# SUPPLY.net
KiCad netlist of a schematic drawn in Altium Designer
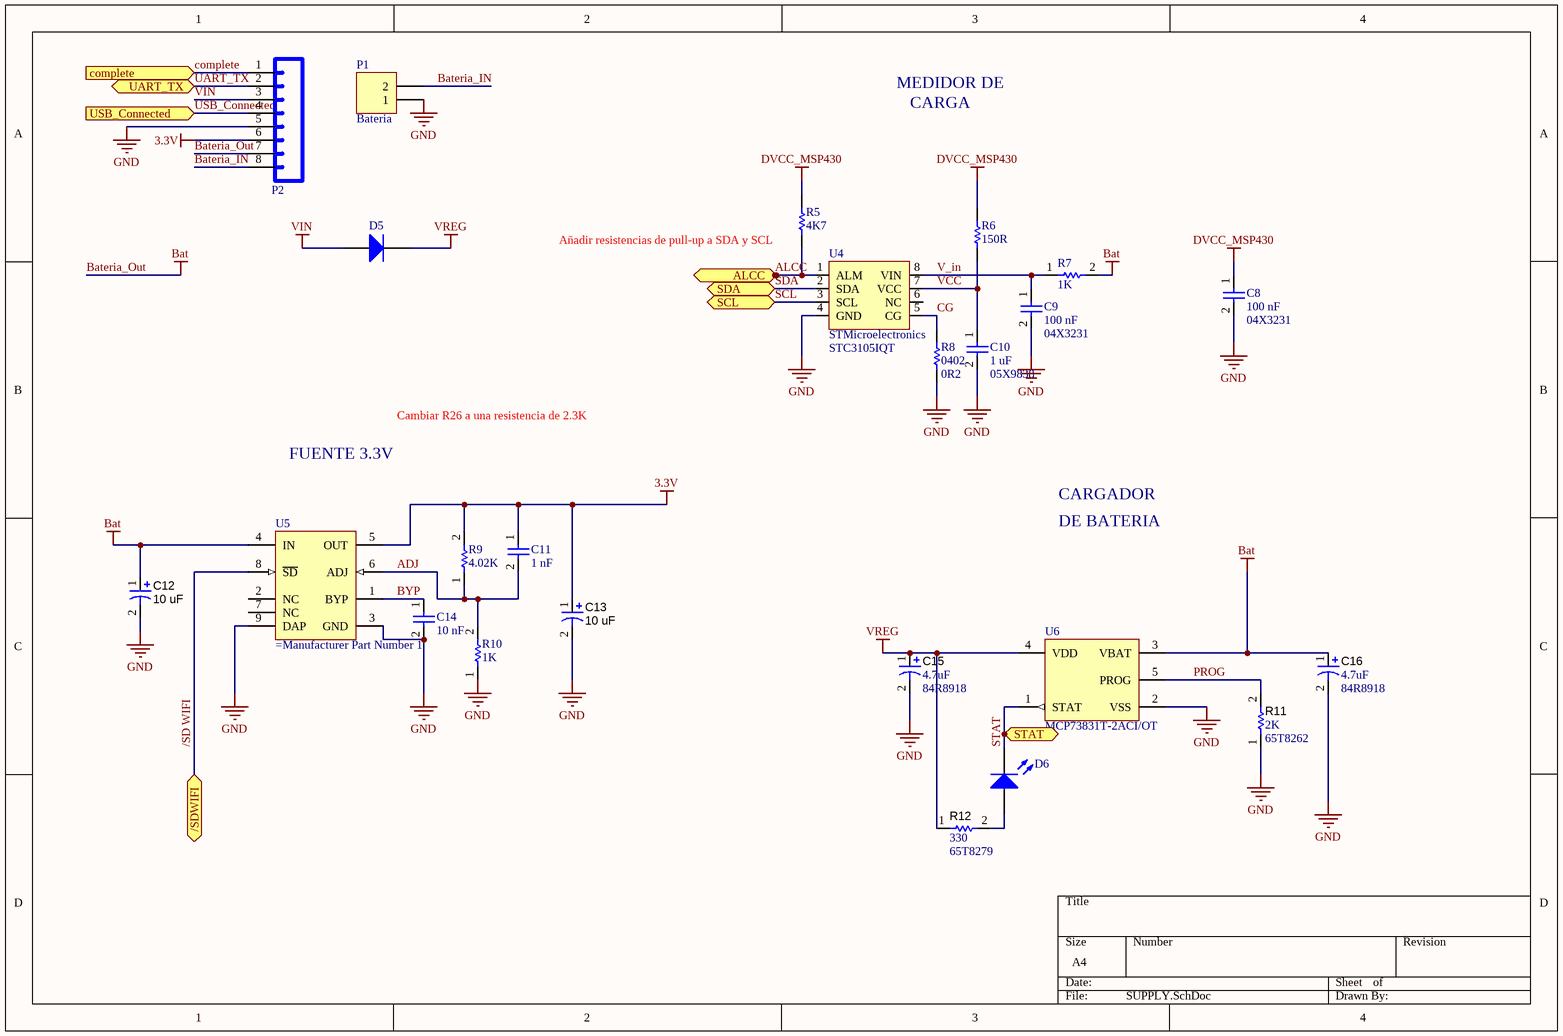
[diagram p0: SUPPLY.SchDoc]

(export (version "E")
  (design (tool "Eeschema 10.0.6"))
  (components
    (comp (ref "C8")
      (value "100 nF")
      (footprint "CR-0402")
      (description "TDK - C1005X7R1H104M050BB - CAP CERAMIC, 0.1UF, 50V, X7R, 0402")
      (fields (field (name "SUPPLIER PART NUMBER 1") "04X3231"))
      (libsource (lib "BASE OXIMETRO") (part "C1005X7R1H104M050BB"))
    )
    (comp (ref "C9")
      (value "100 nF")
      (footprint "CR-0402")
      (description "TDK - C1005X7R1H104M050BB - CAP CERAMIC, 0.1UF, 50V, X7R, 0402")
      (fields (field (name "SUPPLIER PART NUMBER 1") "04X3231"))
      (libsource (lib "BASE OXIMETRO") (part "C1005X7R1H104M050BB"))
    )
    (comp (ref "C10")
      (value "1 uF")
      (footprint "CR-0402")
      (description "TDK - C1005X5R1E105K050BC - CAP, MLCC, X5R, 1UF, 25V, 0402")
      (fields (field (name "SUPPLIER PART NUMBER 1") "05X9838"))
      (libsource (lib "BASE OXIMETRO") (part "C1005X5R1E105K050BC"))
    )
    (comp (ref "C11")
      (value "1 nF")
      (footprint "CR-0402")
      (description "TDK - C1005X7R1E102K050BA - CAPACITOR CERAMIC 1000PF, 25V, X7R, 10%, 0402")
      (libsource (lib "BASE OXIMETRO") (part "C1005X7R1E102K050BA"))
    )
    (comp (ref "C12")
      (value "10 uF")
      (footprint "C-0603")
      (description "NICHICON - F981A106MMA - CAPACITOR TANT, 10UF, 10V 20%")
      (libsource (lib "BASE OXIMETRO") (part "F981A106MMA"))
    )
    (comp (ref "C13")
      (value "10 uF")
      (footprint "C-0603")
      (description "NICHICON - F981A106MMA - CAPACITOR TANT, 10UF, 10V 20%")
      (libsource (lib "BASE OXIMETRO") (part "F981A106MMA"))
    )
    (comp (ref "C14")
      (value "10 nF")
      (footprint "CR-0402")
      (description "TDK - C1005X7R1H103K050BB - CAP CERAMIC, 0.01UF, 50V, X7R, 0402")
      (libsource (lib "BASE OXIMETRO") (part "C1005X7R1H103K050BB"))
    )
    (comp (ref "C15")
      (value "4.7uF")
      (footprint "C-0603")
      (description "CAP, TANTALUM, 4.7UF, 20%, 16V, 20 OHM, SMT0603")
      (fields
        (field (name "PART NUMBER") "F980J475MUA")
        (field (name "MANUFACTURER") "NICHICON")
        (field (name "SUPPLIER PART NUMBER 1") "84R8918")
      )
      (libsource (lib "BASE OXIMETRO") (part "F981C475MMA"))
    )
    (comp (ref "C16")
      (value "4.7uF")
      (footprint "C-0603")
      (description "CAP, TANTALUM, 4.7UF, 20%, 16V, 20 OHM, SMT0603")
      (fields
        (field (name "PART NUMBER") "F980J475MUA")
        (field (name "MANUFACTURER") "NICHICON")
        (field (name "SUPPLIER PART NUMBER 1") "84R8918")
      )
      (libsource (lib "BASE OXIMETRO") (part "F981C475MMA"))
    )
    (comp (ref "D5")
      (value "58K2394")
      (footprint "DO-214AA d")
      (description "Default Diode")
      (fields (field (name "PUBLISHER") "Altium Limited"))
      (libsource (lib "BASE OXIMETRO") (part "Diode"))
    )
    (comp (ref "D6")
      (value "LED0")
      (footprint "CR-0402")
      (description "LED Blue")
      (fields (field (name "PUBLISHER") "Altium Limited"))
      (libsource (lib "BASE OXIMETRO") (part "LED0"))
    )
    (comp (ref "P1")
      (value "Bateria")
      (footprint "HDR1X2")
      (description "Header, 2-Pin")
      (fields (field (name "PUBLISHER") "Altium Limited"))
      (libsource (lib "BASE OXIMETRO") (part "Header 2"))
    )
    (comp (ref "P2")
      (value "68000-236HLF")
      (footprint "HEAD8-NOSS")
      (description "HEADER 1X8")
      (fields (field (name "MANUFACTURER") "Amphenol FCI"))
      (libsource (lib "TarjetaPrincipalV1_4") (part "HEADER 1X8"))
    )
    (comp (ref "R5")
      (value "4K7")
      (footprint "CR-0402")
      (description "VISHAY DALE - CRCW02014K70FNED - THICK FILM RESISTOR, 4.7 KOHM, 50 mW, 1%, FULL REEL")
      (libsource (lib "BASE OXIMETRO") (part "CRCW02014K70FNED"))
    )
    (comp (ref "R6")
      (value "150R")
      (footprint "CR-0402")
      (description "VISHAY DALE - CRCW0201150RFNED - THICK FILM RESISTOR, 150 OHM, 50 mW, 1%, FULL REEL")
      (libsource (lib "BASE OXIMETRO") (part "CRCW0201150RFNED"))
    )
    (comp (ref "R7")
      (value "1K")
      (footprint "CR-0402")
      (description "VISHAY DALE - CRCW02011K00FNED - RESISTOR, THICK FILM CHIP, 1KOHM 50mW, 1%, FULL REEL")
      (libsource (lib "BASE OXIMETRO") (part "CRCW02011K00FNED"))
    )
    (comp (ref "R8")
      (value "0402")
      (footprint "R-0402")
      (description "PANASONIC ELECTRONIC COMPONENTS - ERJ-2BSFR20X - RESISTOR, 0.2OHM, 166mW, 1%, SMD")
      (fields (field (name "ALTIUM_VALUE") "0R2"))
      (libsource (lib "BASE OXIMETRO") (part "ERJ-2BSFR20X"))
    )
    (comp (ref "R9")
      (value "4.02K")
      (footprint "CR-0402")
      (description "VISHAY DALE - CRCW02014K02FNED - RESISTOR, THICK FILM, 4.02 KOHM, 50 mW, 1%, FULL REEL")
      (libsource (lib "BASE OXIMETRO") (part "CRCW02014K02FNED"))
    )
    (comp (ref "R10")
      (value "1K")
      (footprint "CR-0402")
      (description "VISHAY DALE - CRCW02011K00FNED - RESISTOR, THICK FILM CHIP, 1KOHM 50mW, 1%, FULL REEL")
      (libsource (lib "BASE OXIMETRO") (part "CRCW02011K00FNED"))
    )
    (comp (ref "R11")
      (value "2K")
      (footprint "CR-0402")
      (description "RESISTOR, THICK FILM, 2K, 5%, 0.1W, SMT0402")
      (fields
        (field (name "PART NUMBER") "ERJ-2GEJ202X")
        (field (name "PARTNUMBER") "PANASONIC")
        (field (name "SUPPLIER PART NUMBER 1") "65T8262")
      )
      (libsource (lib "BASE OXIMETRO") (part "ERJ-2GEJ202X"))
    )
    (comp (ref "R12")
      (value "330")
      (footprint "R-0402")
      (description "RESISTOR, THICK FILM, 330, 5%, 0.1W, SMT0402")
      (fields
        (field (name "PART NUMBER") "ERJ-2GEJ331X")
        (field (name "MANUFACTURER") "PANASONIC")
        (field (name "SUPPLIER PART NUMBER 1") "65T8279")
      )
      (libsource (lib "BASE OXIMETRO") (part "ERJ-2GEJ331X"))
    )
    (comp (ref "U4")
      (value "STMicroelectronics")
      (footprint "TDFN8")
      (description "IC BATTERY MON GAS GAUGE 8-TDFN")
      (fields (field (name "MANUFACTURER PART NUMBER 1") "STC3105IQT"))
      (libsource (lib "BASE OXIMETRO") (part "STC3105"))
    )
    (comp (ref "U5")
      (value "~")
      (footprint "SO8 DDA")
      (description "TEXAS INSTRUMENTS - LP3878MRX-ADJ/NOPB - IC, LDO REGULATOR, 800mA, 1-5.5V, FULL REEL")
      (libsource (lib "BASE OXIMETRO") (part "LP3878MRX-ADJ/NOPB"))
    )
    (comp (ref "U6")
      (value "MCP73831T-2ACI/OT")
      (footprint "SOT-23-5_3d")
      (fields (field (name "PUBLISHER") "Altium Limited"))
      (libsource (lib "BASE OXIMETRO") (part "MCP73831T-2ACI/OT"))
    )
  )
  (nets
    (net (code "1") (name "/ADJ") (class "Default")
      (node (ref "C11") (pin "2") (pinfunction "2_2") (pintype "passive"))
      (node (ref "R10") (pin "2") (pinfunction "2_2") (pintype "passive"))
      (node (ref "R9") (pin "1") (pinfunction "1_1") (pintype "passive"))
      (node (ref "U5") (pin "6") (pinfunction "ADJ_6") (pintype "input"))
    )
    (net (code "2") (name "/ALCC") (class "Default")
      (node (ref "R5") (pin "1") (pinfunction "1_1") (pintype "passive"))
      (node (ref "U4") (pin "1") (pinfunction "ALM_1") (pintype "passive"))
    )
    (net (code "3") (name "/BYP") (class "Default")
      (node (ref "C14") (pin "1") (pinfunction "1_1") (pintype "passive"))
      (node (ref "U5") (pin "1") (pinfunction "BYP_1") (pintype "passive"))
    )
    (net (code "4") (name "/Bateria_IN") (class "Default")
      (node (ref "P1") (pin "2") (pinfunction "2_2") (pintype "passive"))
      (node (ref "P2") (pin "8") (pinfunction "8_8") (pintype "passive"))
    )
    (net (code "5") (name "/CG") (class "Default")
      (node (ref "R8") (pin "2") (pinfunction "2_2") (pintype "passive"))
      (node (ref "U4") (pin "5") (pinfunction "CG_5") (pintype "passive"))
    )
    (net (code "6") (name "/PROG") (class "Default")
      (node (ref "R11") (pin "2") (pinfunction "2_2") (pintype "passive"))
      (node (ref "U6") (pin "5") (pinfunction "PROG_5") (pintype "passive"))
    )
    (net (code "7") (name "/SCL") (class "Default")
      (node (ref "U4") (pin "3") (pinfunction "SCL_3") (pintype "passive"))
    )
    (net (code "8") (name "/SDA") (class "Default")
      (node (ref "U4") (pin "2") (pinfunction "SDA_2") (pintype "passive"))
    )
    (net (code "9") (name "/STAT") (class "Default")
      (node (ref "D6") (pin "2") (pinfunction "K_2") (pintype "passive"))
      (node (ref "U6") (pin "1") (pinfunction "STAT_1") (pintype "output"))
    )
    (net (code "10") (name "/UART_TX") (class "Default")
      (node (ref "P2") (pin "2") (pinfunction "2_2") (pintype "passive"))
    )
    (net (code "11") (name "/USB_Connected") (class "Default")
      (node (ref "P2") (pin "4") (pinfunction "4_4") (pintype "passive"))
    )
    (net (code "12") (name "/VCC") (class "Default")
      (node (ref "C10") (pin "1") (pinfunction "1_1") (pintype "passive"))
      (node (ref "R6") (pin "1") (pinfunction "1_1") (pintype "passive"))
      (node (ref "U4") (pin "7") (pinfunction "VCC_7") (pintype "passive"))
    )
    (net (code "13") (name "/V_in") (class "Default")
      (node (ref "C9") (pin "1") (pinfunction "1_1") (pintype "passive"))
      (node (ref "R7") (pin "1") (pinfunction "1_1") (pintype "passive"))
      (node (ref "U4") (pin "8") (pinfunction "VIN_8") (pintype "passive"))
    )
    (net (code "14") (name "/complete") (class "Default")
      (node (ref "P2") (pin "1") (pinfunction "1_1") (pintype "passive"))
    )
    (net (code "15") (name "/{slash}SD WIFI") (class "Default")
      (node (ref "U5") (pin "8") (pinfunction "~{SD}_8") (pintype "input"))
    )
    (net (code "16") (name "3.3V") (class "Default")
      (node (ref "C11") (pin "1") (pinfunction "1_1") (pintype "passive"))
      (node (ref "C13") (pin "1") (pinfunction "+_1") (pintype "passive"))
      (node (ref "P2") (pin "6") (pinfunction "6_6") (pintype "passive"))
      (node (ref "R9") (pin "2") (pinfunction "2_2") (pintype "passive"))
      (node (ref "U5") (pin "5") (pinfunction "OUT_5") (pintype "power_in"))
    )
    (net (code "17") (name "Bat") (class "Default")
      (node (ref "C12") (pin "1") (pinfunction "+_1") (pintype "passive"))
      (node (ref "C16") (pin "1") (pinfunction "+_1") (pintype "passive"))
      (node (ref "P2") (pin "7") (pinfunction "7_7") (pintype "passive"))
      (node (ref "R7") (pin "2") (pinfunction "2_2") (pintype "passive"))
      (node (ref "U5") (pin "4") (pinfunction "IN_4") (pintype "power_in"))
      (node (ref "U6") (pin "3") (pinfunction "VBAT_3") (pintype "power_in"))
    )
    (net (code "18") (name "DVCC_MSP430") (class "Default")
      (node (ref "C8") (pin "1") (pinfunction "1_1") (pintype "passive"))
      (node (ref "R5") (pin "2") (pinfunction "2_2") (pintype "passive"))
      (node (ref "R6") (pin "2") (pinfunction "2_2") (pintype "passive"))
    )
    (net (code "19") (name "GND") (class "Default")
      (node (ref "C10") (pin "2") (pinfunction "2_2") (pintype "passive"))
      (node (ref "C12") (pin "2") (pinfunction "-_2") (pintype "passive"))
      (node (ref "C13") (pin "2") (pinfunction "-_2") (pintype "passive"))
      (node (ref "C14") (pin "2") (pinfunction "2_2") (pintype "passive"))
      (node (ref "C15") (pin "2") (pinfunction "-_2") (pintype "passive"))
      (node (ref "C16") (pin "2") (pinfunction "-_2") (pintype "passive"))
      (node (ref "C8") (pin "2") (pinfunction "2_2") (pintype "passive"))
      (node (ref "C9") (pin "2") (pinfunction "2_2") (pintype "passive"))
      (node (ref "P1") (pin "1") (pinfunction "1_1") (pintype "passive"))
      (node (ref "P2") (pin "5") (pinfunction "5_5") (pintype "passive"))
      (node (ref "R10") (pin "1") (pinfunction "1_1") (pintype "passive"))
      (node (ref "R11") (pin "1") (pinfunction "1_1") (pintype "passive"))
      (node (ref "R8") (pin "1") (pinfunction "1_1") (pintype "passive"))
      (node (ref "U4") (pin "4") (pinfunction "GND_4") (pintype "passive"))
      (node (ref "U5") (pin "3") (pinfunction "GND_3") (pintype "power_in"))
      (node (ref "U5") (pin "9") (pinfunction "DAP_9") (pintype "power_in"))
      (node (ref "U6") (pin "2") (pinfunction "VSS_2") (pintype "power_in"))
    )
    (net (code "20") (name "Net-(D6-A)") (class "Default")
      (node (ref "D6") (pin "1") (pinfunction "A_1") (pintype "passive"))
      (node (ref "R12") (pin "2") (pinfunction "2_2") (pintype "passive"))
    )
    (net (code "21") (name "VIN") (class "Default")
      (node (ref "D5") (pin "1") (pinfunction "A_1") (pintype "passive"))
      (node (ref "P2") (pin "3") (pinfunction "3_3") (pintype "passive"))
    )
    (net (code "22") (name "VREG") (class "Default")
      (node (ref "C15") (pin "1") (pinfunction "+_1") (pintype "passive"))
      (node (ref "D5") (pin "2") (pinfunction "K_2") (pintype "passive"))
      (node (ref "R12") (pin "1") (pinfunction "1_1") (pintype "passive"))
      (node (ref "U6") (pin "4") (pinfunction "VDD_4") (pintype "power_in"))
    )
    (net (code "23") (name "unconnected-(U4-NC-Pad6)") (class "Default")
      (node (ref "U4") (pin "6") (pinfunction "NC_6") (pintype "passive"))
    )
    (net (code "24") (name "unconnected-(U5-NC-Pad2)") (class "Default")
      (node (ref "U5") (pin "2") (pinfunction "NC_2") (pintype "passive"))
    )
    (net (code "25") (name "unconnected-(U5-NC-Pad7)") (class "Default")
      (node (ref "U5") (pin "7") (pinfunction "NC_7") (pintype "passive"))
    )
  )
)
